# Logic_Unit.net
KiCad netlist of a schematic drawn in Altium Designer
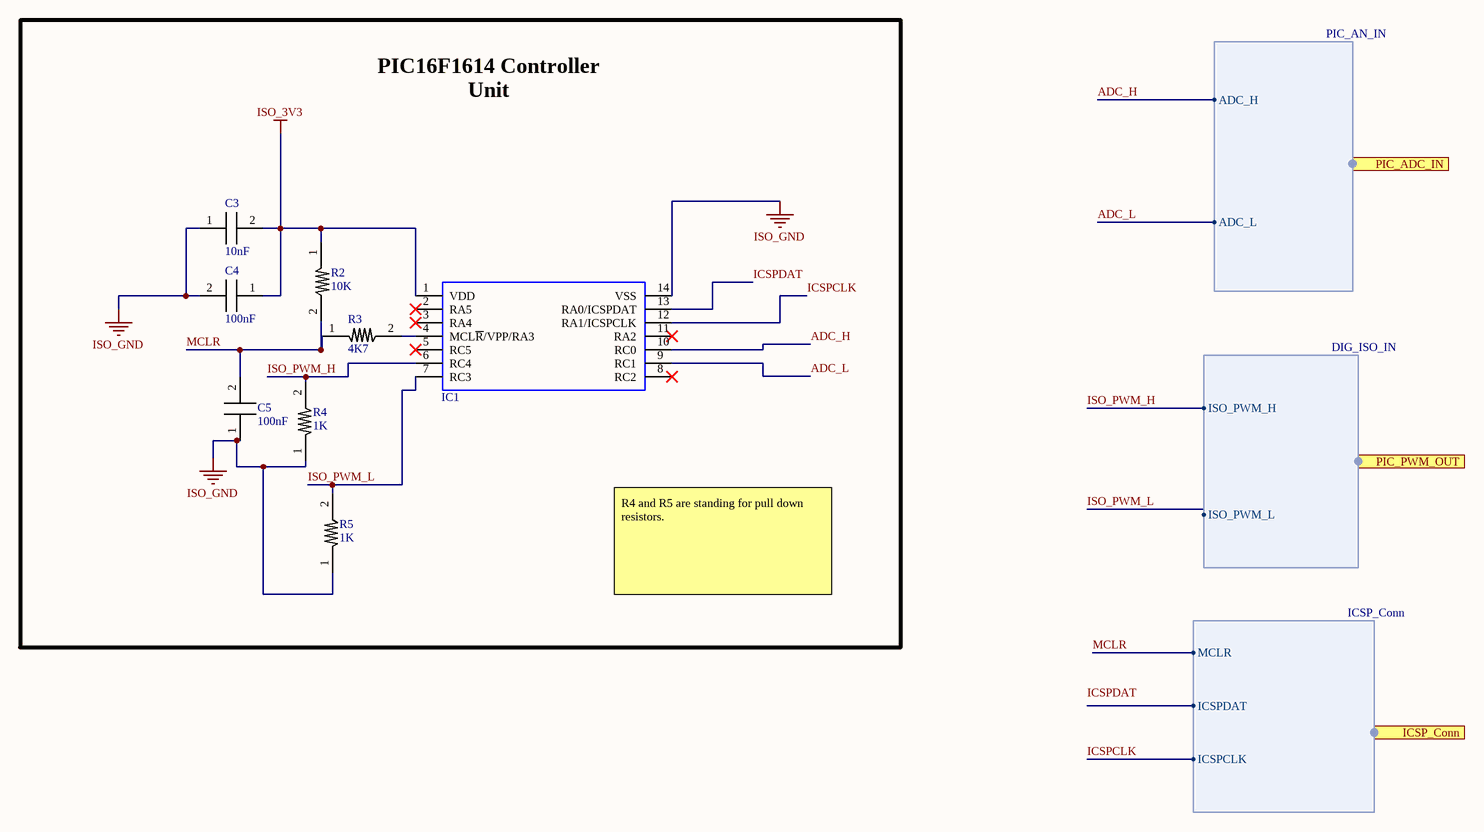
[diagram p0: Logic_Unit.SchDoc]

(export (version "E")
  (design (tool "Eeschema 10.0.6"))
  (components
    (comp (ref "C3")
      (value "CAP 10nF")
      (fields (field (name "PARAMETER 1") "10nF"))
      (libsource (lib "Schlib1") (part "CAP 10nF"))
    )
    (comp (ref "C4")
      (value "CAP 100nF")
      (fields (field (name "PARAMETER 1") "100nF"))
      (libsource (lib "Schlib1") (part "CAP 100nF"))
    )
    (comp (ref "C5")
      (value "CAP 100nF")
      (fields (field (name "PARAMETER 1") "100nF"))
      (libsource (lib "Schlib1") (part "CAP 100nF"))
    )
    (comp (ref "IC1")
      (value "IC PIC16, PIC16F1614")
      (footprint "PIC16F1613")
      (libsource (lib "Schlib1") (part "IC PIC16, PIC16F1614"))
    )
    (comp (ref "R2")
      (value "RES, 10K, 0603")
      (fields (field (name "PARAMETER 1") "10K"))
      (libsource (lib "Schlib1") (part "RES, 10K, 0603"))
    )
    (comp (ref "R3")
      (value "RES, 4K7, 0603")
      (fields (field (name "PARAMETER 1") "4K7"))
      (libsource (lib "Schlib1") (part "RES, 4K7, 0603"))
    )
    (comp (ref "R4")
      (value "RES, 1K, 0603")
      (fields (field (name "PARAMETER 1") "1K"))
      (libsource (lib "Schlib1") (part "RES, 1K, 0603"))
    )
    (comp (ref "R5")
      (value "RES, 1K, 0603")
      (fields (field (name "PARAMETER 1") "1K"))
      (libsource (lib "Schlib1") (part "RES, 1K, 0603"))
    )
  )
  (nets
    (net (code "4") (name "/ADC_H") (class "Default")
      (node (ref "IC1") (pin "10") (pinfunction "RC0_10") (pintype "passive"))
    )
    (net (code "5") (name "/ADC_L") (class "Default")
      (node (ref "IC1") (pin "9") (pinfunction "RC1_9") (pintype "passive"))
    )
    (net (code "6") (name "/ICSPCLK") (class "Default")
      (node (ref "IC1") (pin "12") (pinfunction "RA1/ICSPCLK_12") (pintype "passive"))
    )
    (net (code "7") (name "/ICSPDAT") (class "Default")
      (node (ref "IC1") (pin "13") (pinfunction "RA0/ICSPDAT_13") (pintype "passive"))
    )
    (net (code "8") (name "/ISO_PWM_H") (class "Default")
      (node (ref "IC1") (pin "6") (pinfunction "RC4_6") (pintype "passive"))
      (node (ref "R4") (pin "2") (pinfunction "2_2") (pintype "passive"))
    )
    (net (code "9") (name "/ISO_PWM_L") (class "Default")
      (node (ref "IC1") (pin "7") (pinfunction "RC3_7") (pintype "passive"))
      (node (ref "R5") (pin "2") (pinfunction "2_2") (pintype "passive"))
    )
    (net (code "10") (name "/MCLR") (class "Default")
      (node (ref "C5") (pin "2") (pinfunction "2_2") (pintype "passive"))
      (node (ref "R2") (pin "2") (pinfunction "2_2") (pintype "passive"))
      (node (ref "R3") (pin "1") (pinfunction "1_1") (pintype "passive"))
    )
    (net (code "14") (name "ISO_3V3") (class "Default")
      (node (ref "C3") (pin "2") (pinfunction "2_2") (pintype "passive"))
      (node (ref "C4") (pin "1") (pinfunction "1_1") (pintype "passive"))
      (node (ref "IC1") (pin "1") (pinfunction "VDD_1") (pintype "passive"))
      (node (ref "R2") (pin "1") (pinfunction "1_1") (pintype "passive"))
    )
    (net (code "15") (name "ISO_GND") (class "Default")
      (node (ref "C3") (pin "1") (pinfunction "1_1") (pintype "passive"))
      (node (ref "C4") (pin "2") (pinfunction "2_2") (pintype "passive"))
      (node (ref "C5") (pin "1") (pinfunction "1_1") (pintype "passive"))
      (node (ref "IC1") (pin "14") (pinfunction "VSS_14") (pintype "passive"))
      (node (ref "R4") (pin "1") (pinfunction "1_1") (pintype "passive"))
      (node (ref "R5") (pin "1") (pinfunction "1_1") (pintype "passive"))
    )
    (net (code "16") (name "Net-(IC1-MCL~{R}{slash}VPP{slash}RA3)") (class "Default")
      (node (ref "IC1") (pin "4") (pinfunction "MCL~{R}/VPP/RA3_4") (pintype "passive"))
      (node (ref "R3") (pin "2") (pinfunction "2_2") (pintype "passive"))
    )
    (net (code "17") (name "unconnected-(IC1-RA2-Pad11)") (class "Default")
      (node (ref "IC1") (pin "11") (pinfunction "RA2_11") (pintype "passive+no_connect"))
    )
    (net (code "18") (name "unconnected-(IC1-RA4-Pad3)") (class "Default")
      (node (ref "IC1") (pin "3") (pinfunction "RA4_3") (pintype "passive+no_connect"))
    )
    (net (code "19") (name "unconnected-(IC1-RA5-Pad2)") (class "Default")
      (node (ref "IC1") (pin "2") (pinfunction "RA5_2") (pintype "passive+no_connect"))
    )
    (net (code "20") (name "unconnected-(IC1-RC2-Pad8)") (class "Default")
      (node (ref "IC1") (pin "8") (pinfunction "RC2_8") (pintype "passive+no_connect"))
    )
    (net (code "21") (name "unconnected-(IC1-RC5-Pad5)") (class "Default")
      (node (ref "IC1") (pin "5") (pinfunction "RC5_5") (pintype "passive+no_connect"))
    )
  )
)
